# TYPEC0_Connector.net
KiCad netlist of a schematic drawn in Altium Designer
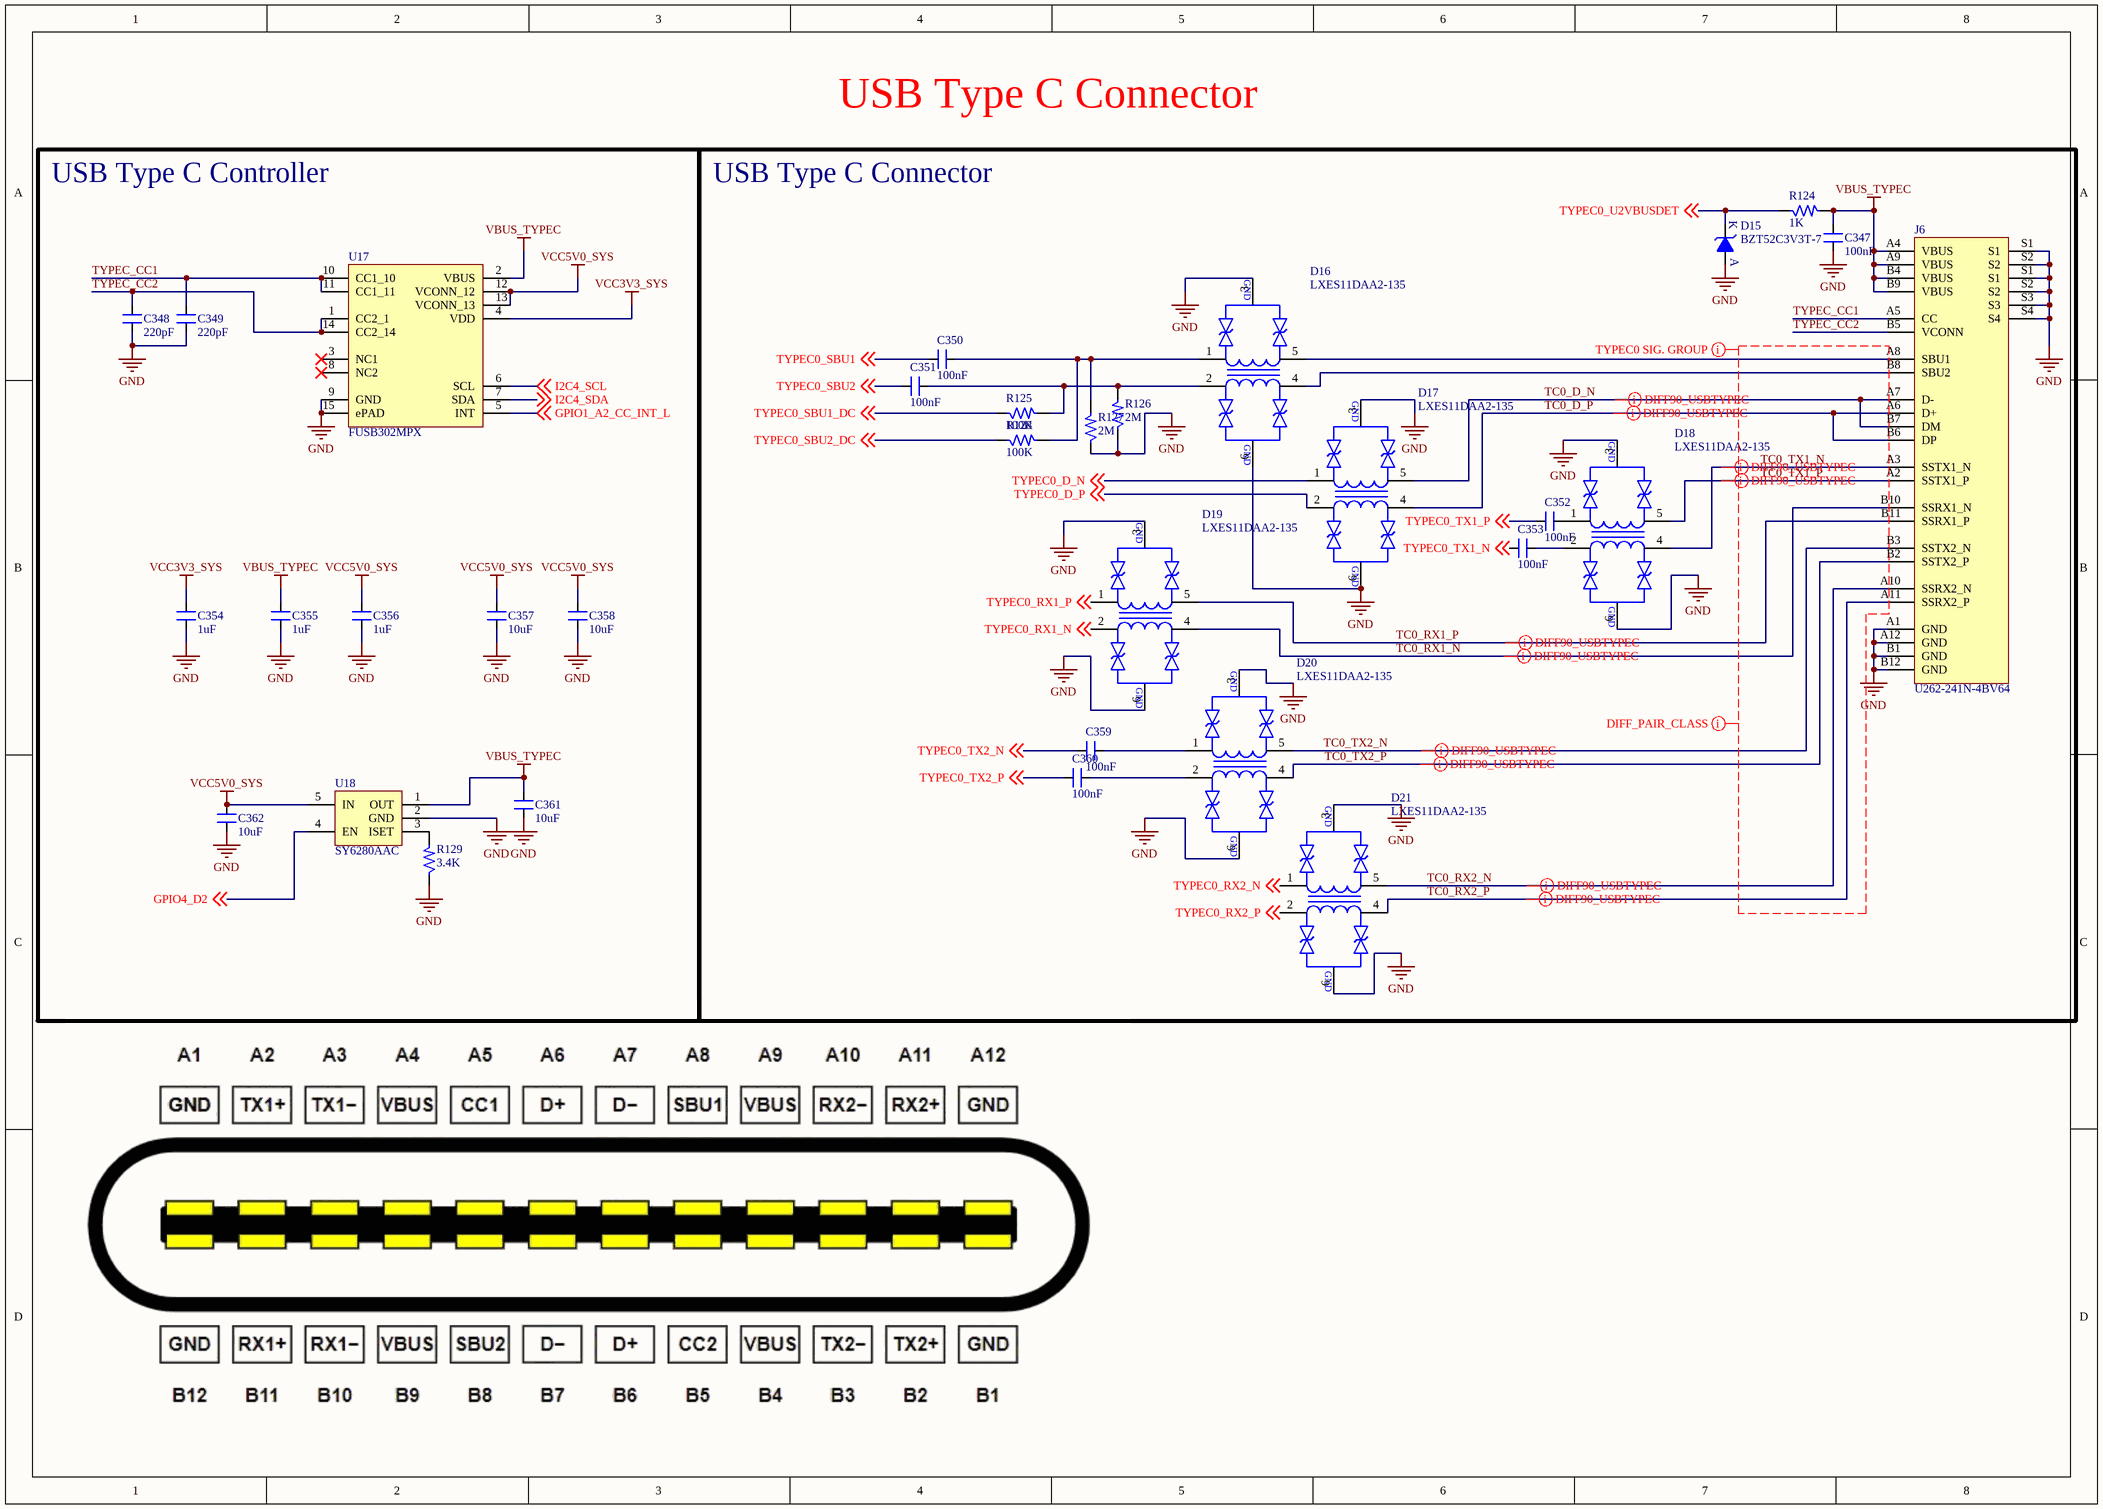
[diagram p0: TYPEC0 Connector.SchDoc]

(export (version "E")
  (design (tool "Eeschema 10.0.6"))
  (components
    (comp (ref "C347")
      (value "100nF")
      (footprint "CAP_0603")
      (description "0.1µF ±10% 10V Ceramic Capacitor X7R 0603 (1608 Metric)")
      (fields
        (field (name "MANUFACTURER") "Yageo")
        (field (name "MANUFACTURER PART NUMBER") "CC0603KRX7R6BB104")
      )
      (libsource (lib "RK3399 _Module_Schlib") (part "CAP_100nF-10V-5%-0603"))
    )
    (comp (ref "C348")
      (value "220pF")
      (footprint "CAP_0603")
      (description "220pF ±10% 10V Ceramic Capacitor X7R 0603 (1608 Metric)")
      (fields
        (field (name "MANUFACTURER") "KEMET")
        (field (name "MANUFACTURER PART NUMBER") "C0603C221K8RAC7867")
      )
      (libsource (lib "RK3399 _Module_Schlib") (part "CAP_220pF-10V-10%-0603"))
    )
    (comp (ref "C349")
      (value "220pF")
      (footprint "CAP_0603")
      (description "220pF ±10% 10V Ceramic Capacitor X7R 0603 (1608 Metric)")
      (fields
        (field (name "MANUFACTURER") "KEMET")
        (field (name "MANUFACTURER PART NUMBER") "C0603C221K8RAC7867")
      )
      (libsource (lib "RK3399 _Module_Schlib") (part "CAP_220pF-10V-10%-0603"))
    )
    (comp (ref "C350")
      (value "100nF")
      (footprint "CAP_0402")
      (description "0.1µF ±10% 10V Ceramic Capacitor X7R 0402 (1005 Metric)")
      (fields
        (field (name "MANUFACTURER") "Yageo")
        (field (name "MANUFACTURER PART NUMBER") "CC0402KRX7R6BB104")
      )
      (libsource (lib "RK3399 _Module_Schlib") (part "CAP_100nF-10V-10%-0402"))
    )
    (comp (ref "C351")
      (value "100nF")
      (footprint "CAP_0402")
      (description "0.1µF ±10% 10V Ceramic Capacitor X7R 0402 (1005 Metric)")
      (fields
        (field (name "MANUFACTURER") "Yageo")
        (field (name "MANUFACTURER PART NUMBER") "CC0402KRX7R6BB104")
      )
      (libsource (lib "RK3399 _Module_Schlib") (part "CAP_100nF-10V-10%-0402"))
    )
    (comp (ref "C352")
      (value "100nF")
      (footprint "CAP_0402")
      (description "0.1µF ±10% 10V Ceramic Capacitor X7R 0402 (1005 Metric)")
      (fields
        (field (name "MANUFACTURER") "Yageo")
        (field (name "MANUFACTURER PART NUMBER") "CC0402KRX7R6BB104")
      )
      (libsource (lib "RK3399 _Module_Schlib") (part "CAP_100nF-10V-10%-0402"))
    )
    (comp (ref "C353")
      (value "100nF")
      (footprint "CAP_0402")
      (description "0.1µF ±10% 10V Ceramic Capacitor X7R 0402 (1005 Metric)")
      (fields
        (field (name "MANUFACTURER") "Yageo")
        (field (name "MANUFACTURER PART NUMBER") "CC0402KRX7R6BB104")
      )
      (libsource (lib "RK3399 _Module_Schlib") (part "CAP_100nF-10V-10%-0402"))
    )
    (comp (ref "C354")
      (value "1uF")
      (footprint "CAP_0603")
      (description "1µF ±10% 10V Ceramic Capacitor X5R 0603 (1608 Metric)")
      (fields
        (field (name "MANUFACTURER") "Samsung Electro-Mechanics")
        (field (name "MANUFACTURER PART NUMBER") "CL10A105KP8NNNC")
      )
      (libsource (lib "RK3399 _Module_Schlib") (part "CAP_1uF-10V-5%-0603"))
    )
    (comp (ref "C355")
      (value "1uF")
      (footprint "CAP_0603")
      (description "1µF ±10% 10V Ceramic Capacitor X5R 0603 (1608 Metric)")
      (fields
        (field (name "MANUFACTURER") "Samsung Electro-Mechanics")
        (field (name "MANUFACTURER PART NUMBER") "CL10A105KP8NNNC")
      )
      (libsource (lib "RK3399 _Module_Schlib") (part "CAP_1uF-10V-5%-0603"))
    )
    (comp (ref "C356")
      (value "1uF")
      (footprint "CAP_0603")
      (description "1µF ±10% 10V Ceramic Capacitor X5R 0603 (1608 Metric)")
      (fields
        (field (name "MANUFACTURER") "Samsung Electro-Mechanics")
        (field (name "MANUFACTURER PART NUMBER") "CL10A105KP8NNNC")
      )
      (libsource (lib "RK3399 _Module_Schlib") (part "CAP_1uF-10V-5%-0603"))
    )
    (comp (ref "C357")
      (value "10uF")
      (footprint "CAP_0805")
      (description "10µF ±10% 25V Ceramic Capacitor X5R 0805 (2012 Metric)")
      (fields
        (field (name "MANUFACTURER") "Murata Electronics")
        (field (name "MANUFACTURER PART NUMBER") "GRM21BR61E106KA73K")
      )
      (libsource (lib "RK3399 _Module_Schlib") (part "CAP_10uF-25V-10%-0805"))
    )
    (comp (ref "C358")
      (value "10uF")
      (footprint "CAP_0805")
      (description "10µF ±10% 25V Ceramic Capacitor X5R 0805 (2012 Metric)")
      (fields
        (field (name "MANUFACTURER") "Murata Electronics")
        (field (name "MANUFACTURER PART NUMBER") "GRM21BR61E106KA73K")
      )
      (libsource (lib "RK3399 _Module_Schlib") (part "CAP_10uF-25V-10%-0805"))
    )
    (comp (ref "C359")
      (value "100nF")
      (footprint "CAP_0402")
      (description "0.1µF ±10% 10V Ceramic Capacitor X7R 0402 (1005 Metric)")
      (fields
        (field (name "MANUFACTURER") "Yageo")
        (field (name "MANUFACTURER PART NUMBER") "CC0402KRX7R6BB104")
      )
      (libsource (lib "RK3399 _Module_Schlib") (part "CAP_100nF-10V-10%-0402"))
    )
    (comp (ref "C360")
      (value "100nF")
      (footprint "CAP_0402")
      (description "0.1µF ±10% 10V Ceramic Capacitor X7R 0402 (1005 Metric)")
      (fields
        (field (name "MANUFACTURER") "Yageo")
        (field (name "MANUFACTURER PART NUMBER") "CC0402KRX7R6BB104")
      )
      (libsource (lib "RK3399 _Module_Schlib") (part "CAP_100nF-10V-10%-0402"))
    )
    (comp (ref "C361")
      (value "10uF")
      (footprint "CAP_0805")
      (description "10µF ±10% 25V Ceramic Capacitor X5R 0805 (2012 Metric)")
      (fields
        (field (name "MANUFACTURER") "Murata Electronics")
        (field (name "MANUFACTURER PART NUMBER") "GRM21BR61E106KA73K")
      )
      (libsource (lib "RK3399 _Module_Schlib") (part "CAP_10uF-25V-10%-0805"))
    )
    (comp (ref "C362")
      (value "10uF")
      (footprint "CAP_0805")
      (description "10µF ±10% 25V Ceramic Capacitor X5R 0805 (2012 Metric)")
      (fields
        (field (name "MANUFACTURER") "Murata Electronics")
        (field (name "MANUFACTURER PART NUMBER") "GRM21BR61E106KA73K")
      )
      (libsource (lib "RK3399 _Module_Schlib") (part "CAP_10uF-25V-10%-0805"))
    )
    (comp (ref "D15")
      (value "BZT52C3V3T-7")
      (footprint "DIO_SOD523")
      (description "Zener Diode 3.3V 300mW ±6% Surface Mount SOD-523")
      (fields (field (name "MANUFACTURER") "Diodes Incorporated"))
      (libsource (lib "RK3399 _Module_Schlib") (part "DIO-Z_3.3V-300mW-SOD-523"))
    )
    (comp (ref "D16")
      (value "LXES11DAA2-135")
      (footprint "DIO_LXES11D_SMD")
      (description "Clamp Ipp Tvs Diode Surface Mount 10-SMD")
      (fields (field (name "MANUFACTURER") "Murata Electronics"))
      (libsource (lib "RK3399 _Module_Schlib") (part "DIO-T-A_5V-6SMD"))
    )
    (comp (ref "D17")
      (value "LXES11DAA2-135")
      (footprint "DIO_LXES11D_SMD")
      (description "Clamp Ipp Tvs Diode Surface Mount 10-SMD")
      (fields (field (name "MANUFACTURER") "Murata Electronics"))
      (libsource (lib "RK3399 _Module_Schlib") (part "DIO-T-A_5V-6SMD"))
    )
    (comp (ref "D18")
      (value "LXES11DAA2-135")
      (footprint "DIO_LXES11D_SMD")
      (description "Clamp Ipp Tvs Diode Surface Mount 10-SMD")
      (fields (field (name "MANUFACTURER") "Murata Electronics"))
      (libsource (lib "RK3399 _Module_Schlib") (part "DIO-T-A_5V-6SMD"))
    )
    (comp (ref "D19")
      (value "LXES11DAA2-135")
      (footprint "DIO_LXES11D_SMD")
      (description "Clamp Ipp Tvs Diode Surface Mount 10-SMD")
      (fields (field (name "MANUFACTURER") "Murata Electronics"))
      (libsource (lib "RK3399 _Module_Schlib") (part "DIO-T-A_5V-6SMD"))
    )
    (comp (ref "D20")
      (value "LXES11DAA2-135")
      (footprint "DIO_LXES11D_SMD")
      (description "Clamp Ipp Tvs Diode Surface Mount 10-SMD")
      (fields (field (name "MANUFACTURER") "Murata Electronics"))
      (libsource (lib "RK3399 _Module_Schlib") (part "DIO-T-A_5V-6SMD"))
    )
    (comp (ref "D21")
      (value "LXES11DAA2-135")
      (footprint "DIO_LXES11D_SMD")
      (description "Clamp Ipp Tvs Diode Surface Mount 10-SMD")
      (fields (field (name "MANUFACTURER") "Murata Electronics"))
      (libsource (lib "RK3399 _Module_Schlib") (part "DIO-T-A_5V-6SMD"))
    )
    (comp (ref "J6")
      (value "U262-241N-4BV64")
      (footprint "CON24_19.64_U262-241N-4BV64_TH_RA")
      (description "USB - Type C Female 24 SMD USB Connectors RoHS")
      (fields (field (name "MANUFACTURER") "XKB Connectivity"))
      (libsource (lib "RK3399 _Module_Schlib") (part "CON-TYPEC_U262-241N-4BV64-SMD"))
    )
    (comp (ref "R124")
      (value "1K")
      (footprint "RES_0603")
      (description "1 kOhms ±1% 0.1W, 1/10W Chip Resistor 0603 (1608 Metric) Thick Film")
      (fields
        (field (name "MANUFACTURER") "Yageo")
        (field (name "MANUFACTURER PART NUMBER") "RC0603FR-071KL")
      )
      (libsource (lib "RK3399 _Module_Schlib") (part "RES_1K-0.1W-1%-0603"))
    )
    (comp (ref "R125")
      (value "100K")
      (footprint "RES_0603")
      (description "100 kOhms ±1% 0.1W, 1/10W Chip Resistor 0603 (1608 Metric) Automotive AEC-Q200 Thick Film")
      (fields
        (field (name "MANUFACTURER") "tackpole Electronics Inc")
        (field (name "MANUFACTURER PART NUMBER") "RMCF0603FT100K")
      )
      (libsource (lib "RK3399 _Module_Schlib") (part "RES_100K-0.1W-1%-0603"))
    )
    (comp (ref "R126")
      (value "2M")
      (footprint "RES_0603")
      (fields
        (field (name "MANUFACTURER") "KOA Speer Electronics, Inc.")
        (field (name "MANUFACTURER PART NUMBER") "RK73H1JTTD2004F")
      )
      (libsource (lib "RK3399 _Module_Schlib") (part "RES_2M-0.1W-1%-0603"))
    )
    (comp (ref "R127")
      (value "2M")
      (footprint "RES_0603")
      (fields
        (field (name "MANUFACTURER") "KOA Speer Electronics, Inc.")
        (field (name "MANUFACTURER PART NUMBER") "RK73H1JTTD2004F")
      )
      (libsource (lib "RK3399 _Module_Schlib") (part "RES_2M-0.1W-1%-0603"))
    )
    (comp (ref "R128")
      (value "100K")
      (footprint "RES_0603")
      (description "100 kOhms ±1% 0.1W, 1/10W Chip Resistor 0603 (1608 Metric) Automotive AEC-Q200 Thick Film")
      (fields
        (field (name "MANUFACTURER") "tackpole Electronics Inc")
        (field (name "MANUFACTURER PART NUMBER") "RMCF0603FT100K")
      )
      (libsource (lib "RK3399 _Module_Schlib") (part "RES_100K-0.1W-1%-0603"))
    )
    (comp (ref "R129")
      (value "3.4K")
      (footprint "RES_0603")
      (description "3.4 kOhms ±1% 0.1W, 1/10W Chip Resistor 0603 (1608 Metric) Automotive AEC-Q200 Thick Film")
      (fields
        (field (name "MANUFACTURER") "Stackpole Electronics Inc")
        (field (name "MANUFACTURER PART NUMBER") "RMCF0603FT3K40")
      )
      (libsource (lib "RK3399 _Module_Schlib") (part "RES_3.4K-0.1W-1%-0603"))
    )
    (comp (ref "U17")
      (value "FUSB302MPX")
      (footprint "MLP-14_98.4X98.4_SMD")
      (description "USB Controller USB 3.1 USB Interface 14-MLP (2.5x2.5)")
      (fields (field (name "MANUFACTURER") "ON Semiconductor"))
      (libsource (lib "RK3399 _Module_Schlib") (part "IC_FUSB302MPX"))
    )
    (comp (ref "U18")
      (value "SY6280AAC")
      (footprint "SOT23-5")
      (description "SOT-23-5 PMIC - Power Distribution Switches RoHS")
      (fields (field (name "MANUFACTURER") "Silergy Corp"))
      (libsource (lib "RK3399 _Module_Schlib") (part "REG-ADJ_5.5V-5.5V-1.25A-SOT-23-5"))
    )
  )
  (nets
    (net (code "1") (name "/TC0_D_N") (class "Default")
      (node (ref "D17") (pin "5") (pinfunction "5_5") (pintype "passive"))
      (node (ref "J6") (pin "A7") (pinfunction "D-_A7") (pintype "passive"))
      (node (ref "J6") (pin "B7") (pinfunction "DM_B7") (pintype "passive"))
    )
    (net (code "2") (name "/TC0_D_P") (class "Default")
      (node (ref "D17") (pin "4") (pinfunction "4_4") (pintype "passive"))
      (node (ref "J6") (pin "A6") (pinfunction "D+_A6") (pintype "passive"))
      (node (ref "J6") (pin "B6") (pinfunction "DP_B6") (pintype "passive"))
    )
    (net (code "3") (name "/TC0_RX1_N") (class "Default")
      (node (ref "D19") (pin "4") (pinfunction "4_4") (pintype "passive"))
      (node (ref "J6") (pin "B10") (pinfunction "SSRX1_N_B10") (pintype "passive"))
    )
    (net (code "4") (name "/TC0_RX1_P") (class "Default")
      (node (ref "D19") (pin "5") (pinfunction "5_5") (pintype "passive"))
      (node (ref "J6") (pin "B11") (pinfunction "SSRX1_P_B11") (pintype "passive"))
    )
    (net (code "5") (name "/TC0_RX2_N") (class "Default")
      (node (ref "D21") (pin "5") (pinfunction "5_5") (pintype "passive"))
      (node (ref "J6") (pin "A10") (pinfunction "SSRX2_N_A10") (pintype "passive"))
    )
    (net (code "6") (name "/TC0_RX2_P") (class "Default")
      (node (ref "D21") (pin "4") (pinfunction "4_4") (pintype "passive"))
      (node (ref "J6") (pin "A11") (pinfunction "SSRX2_P_A11") (pintype "passive"))
    )
    (net (code "7") (name "/TC0_TX1_N") (class "Default")
      (node (ref "D18") (pin "4") (pinfunction "4_4") (pintype "passive"))
      (node (ref "J6") (pin "A3") (pinfunction "SSTX1_N_A3") (pintype "passive"))
    )
    (net (code "8") (name "/TC0_TX1_P") (class "Default")
      (node (ref "D18") (pin "5") (pinfunction "5_5") (pintype "passive"))
      (node (ref "J6") (pin "A2") (pinfunction "SSTX1_P_A2") (pintype "passive"))
    )
    (net (code "9") (name "/TC0_TX2_N") (class "Default")
      (node (ref "D20") (pin "5") (pinfunction "5_5") (pintype "passive"))
      (node (ref "J6") (pin "B3") (pinfunction "SSTX2_N_B3") (pintype "passive"))
    )
    (net (code "10") (name "/TC0_TX2_P") (class "Default")
      (node (ref "D20") (pin "4") (pinfunction "4_4") (pintype "passive"))
      (node (ref "J6") (pin "B2") (pinfunction "SSTX2_P_B2") (pintype "passive"))
    )
    (net (code "11") (name "/TYPEC_CC1") (class "Default")
      (node (ref "C349") (pin "2") (pinfunction "2_2") (pintype "passive"))
      (node (ref "J6") (pin "A5") (pinfunction "CC_A5") (pintype "passive"))
      (node (ref "U17") (pin "10") (pinfunction "CC1_10_10") (pintype "passive"))
      (node (ref "U17") (pin "11") (pinfunction "CC1_11_11") (pintype "passive"))
    )
    (net (code "12") (name "/TYPEC_CC2") (class "Default")
      (node (ref "C348") (pin "2") (pinfunction "2_2") (pintype "passive"))
      (node (ref "J6") (pin "B5") (pinfunction "VCONN_B5") (pintype "passive"))
      (node (ref "U17") (pin "1") (pinfunction "CC2_1_1") (pintype "passive"))
      (node (ref "U17") (pin "14") (pinfunction "CC2_14_14") (pintype "passive"))
    )
    (net (code "13") (name "GND") (class "Default")
      (node (ref "C347") (pin "1") (pinfunction "1_1") (pintype "passive"))
      (node (ref "C348") (pin "1") (pinfunction "1_1") (pintype "passive"))
      (node (ref "C349") (pin "1") (pinfunction "1_1") (pintype "passive"))
      (node (ref "C354") (pin "1") (pinfunction "1_1") (pintype "passive"))
      (node (ref "C355") (pin "1") (pinfunction "1_1") (pintype "passive"))
      (node (ref "C356") (pin "1") (pinfunction "1_1") (pintype "passive"))
      (node (ref "C357") (pin "1") (pinfunction "1_1") (pintype "passive"))
      (node (ref "C358") (pin "1") (pinfunction "1_1") (pintype "passive"))
      (node (ref "C361") (pin "1") (pinfunction "1_1") (pintype "passive"))
      (node (ref "C362") (pin "1") (pinfunction "1_1") (pintype "passive"))
      (node (ref "D15") (pin "A") (pinfunction "A_A") (pintype "passive"))
      (node (ref "D16") (pin "3") (pinfunction "5_3") (pintype "passive"))
      (node (ref "D16") (pin "6") (pinfunction "6_6") (pintype "passive"))
      (node (ref "D17") (pin "3") (pinfunction "5_3") (pintype "passive"))
      (node (ref "D17") (pin "6") (pinfunction "6_6") (pintype "passive"))
      (node (ref "D18") (pin "3") (pinfunction "5_3") (pintype "passive"))
      (node (ref "D18") (pin "6") (pinfunction "6_6") (pintype "passive"))
      (node (ref "D19") (pin "3") (pinfunction "5_3") (pintype "passive"))
      (node (ref "D19") (pin "6") (pinfunction "6_6") (pintype "passive"))
      (node (ref "D20") (pin "3") (pinfunction "5_3") (pintype "passive"))
      (node (ref "D20") (pin "6") (pinfunction "6_6") (pintype "passive"))
      (node (ref "D21") (pin "3") (pinfunction "5_3") (pintype "passive"))
      (node (ref "D21") (pin "6") (pinfunction "6_6") (pintype "passive"))
      (node (ref "J6") (pin "A1") (pinfunction "GND_A1") (pintype "passive"))
      (node (ref "J6") (pin "A12") (pinfunction "GND_A12") (pintype "passive"))
      (node (ref "J6") (pin "B1") (pinfunction "GND_B1") (pintype "passive"))
      (node (ref "J6") (pin "B12") (pinfunction "GND_B12") (pintype "passive"))
      (node (ref "J6") (pin "S1") (pinfunction "S1_S1") (pintype "passive"))
      (node (ref "J6") (pin "S2") (pinfunction "S2_S2") (pintype "passive"))
      (node (ref "J6") (pin "S3") (pinfunction "S3_S3") (pintype "passive"))
      (node (ref "J6") (pin "S4") (pinfunction "S4_S4") (pintype "passive"))
      (node (ref "R126") (pin "1") (pinfunction "1_1") (pintype "passive"))
      (node (ref "R127") (pin "1") (pinfunction "1_1") (pintype "passive"))
      (node (ref "R129") (pin "1") (pinfunction "1_1") (pintype "passive"))
      (node (ref "U17") (pin "15") (pinfunction "ePAD_15") (pintype "passive"))
      (node (ref "U17") (pin "9") (pinfunction "GND_9") (pintype "passive"))
      (node (ref "U18") (pin "2") (pinfunction "GND_2") (pintype "passive"))
    )
    (net (code "14") (name "GPIO1_A2_CC_INT_L") (class "Default")
      (node (ref "U17") (pin "5") (pinfunction "INT_5") (pintype "passive"))
    )
    (net (code "15") (name "GPIO4_D2") (class "Default")
      (node (ref "U18") (pin "4") (pinfunction "EN_4") (pintype "passive"))
    )
    (net (code "16") (name "I2C4_SCL") (class "Default")
      (node (ref "U17") (pin "6") (pinfunction "SCL_6") (pintype "passive"))
    )
    (net (code "17") (name "I2C4_SDA") (class "Default")
      (node (ref "U17") (pin "7") (pinfunction "SDA_7") (pintype "passive"))
    )
    (net (code "18") (name "Net-(C350-Pad2)") (class "Default")
      (node (ref "C350") (pin "2") (pinfunction "2_2") (pintype "passive"))
      (node (ref "D16") (pin "1") (pinfunction "1_1") (pintype "passive"))
      (node (ref "R127") (pin "2") (pinfunction "2_2") (pintype "passive"))
      (node (ref "R128") (pin "2") (pinfunction "2_2") (pintype "passive"))
    )
    (net (code "19") (name "Net-(C351-Pad2)") (class "Default")
      (node (ref "C351") (pin "2") (pinfunction "2_2") (pintype "passive"))
      (node (ref "D16") (pin "2") (pinfunction "2_2") (pintype "passive"))
      (node (ref "R125") (pin "2") (pinfunction "2_2") (pintype "passive"))
      (node (ref "R126") (pin "2") (pinfunction "2_2") (pintype "passive"))
    )
    (net (code "20") (name "Net-(C352-Pad2)") (class "Default")
      (node (ref "C352") (pin "2") (pinfunction "2_2") (pintype "passive"))
      (node (ref "D18") (pin "1") (pinfunction "1_1") (pintype "passive"))
    )
    (net (code "21") (name "Net-(C353-Pad2)") (class "Default")
      (node (ref "C353") (pin "2") (pinfunction "2_2") (pintype "passive"))
      (node (ref "D18") (pin "2") (pinfunction "2_2") (pintype "passive"))
    )
    (net (code "22") (name "Net-(C359-Pad2)") (class "Default")
      (node (ref "C359") (pin "2") (pinfunction "2_2") (pintype "passive"))
      (node (ref "D20") (pin "1") (pinfunction "1_1") (pintype "passive"))
    )
    (net (code "23") (name "Net-(C360-Pad2)") (class "Default")
      (node (ref "C360") (pin "2") (pinfunction "2_2") (pintype "passive"))
      (node (ref "D20") (pin "2") (pinfunction "2_2") (pintype "passive"))
    )
    (net (code "24") (name "Net-(J6-SBU1)") (class "Default")
      (node (ref "D16") (pin "5") (pinfunction "5_5") (pintype "passive"))
      (node (ref "J6") (pin "A8") (pinfunction "SBU1_A8") (pintype "passive"))
    )
    (net (code "25") (name "Net-(J6-SBU2)") (class "Default")
      (node (ref "D16") (pin "4") (pinfunction "4_4") (pintype "passive"))
      (node (ref "J6") (pin "B8") (pinfunction "SBU2_B8") (pintype "passive"))
    )
    (net (code "26") (name "Net-(U18-ISET)") (class "Default")
      (node (ref "R129") (pin "2") (pinfunction "2_2") (pintype "passive"))
      (node (ref "U18") (pin "3") (pinfunction "ISET_3") (pintype "passive"))
    )
    (net (code "27") (name "TYPEC0_D_N") (class "Default")
      (node (ref "D17") (pin "1") (pinfunction "1_1") (pintype "passive"))
    )
    (net (code "28") (name "TYPEC0_D_P") (class "Default")
      (node (ref "D17") (pin "2") (pinfunction "2_2") (pintype "passive"))
    )
    (net (code "29") (name "TYPEC0_RX1_N") (class "Default")
      (node (ref "D19") (pin "2") (pinfunction "2_2") (pintype "passive"))
    )
    (net (code "30") (name "TYPEC0_RX1_P") (class "Default")
      (node (ref "D19") (pin "1") (pinfunction "1_1") (pintype "passive"))
    )
    (net (code "31") (name "TYPEC0_RX2_N") (class "Default")
      (node (ref "D21") (pin "1") (pinfunction "1_1") (pintype "passive"))
    )
    (net (code "32") (name "TYPEC0_RX2_P") (class "Default")
      (node (ref "D21") (pin "2") (pinfunction "2_2") (pintype "passive"))
    )
    (net (code "33") (name "TYPEC0_SBU1") (class "Default")
      (node (ref "C350") (pin "1") (pinfunction "1_1") (pintype "passive"))
    )
    (net (code "34") (name "TYPEC0_SBU1_DC") (class "Default")
      (node (ref "R125") (pin "1") (pinfunction "1_1") (pintype "passive"))
    )
    (net (code "35") (name "TYPEC0_SBU2") (class "Default")
      (node (ref "C351") (pin "1") (pinfunction "1_1") (pintype "passive"))
    )
    (net (code "36") (name "TYPEC0_SBU2_DC") (class "Default")
      (node (ref "R128") (pin "1") (pinfunction "1_1") (pintype "passive"))
    )
    (net (code "37") (name "TYPEC0_TX1_N") (class "Default")
      (node (ref "C353") (pin "1") (pinfunction "1_1") (pintype "passive"))
    )
    (net (code "38") (name "TYPEC0_TX1_P") (class "Default")
      (node (ref "C352") (pin "1") (pinfunction "1_1") (pintype "passive"))
    )
    (net (code "39") (name "TYPEC0_TX2_N") (class "Default")
      (node (ref "C359") (pin "1") (pinfunction "1_1") (pintype "passive"))
    )
    (net (code "40") (name "TYPEC0_TX2_P") (class "Default")
      (node (ref "C360") (pin "1") (pinfunction "1_1") (pintype "passive"))
    )
    (net (code "41") (name "TYPEC0_U2VBUSDET") (class "Default")
      (node (ref "D15") (pin "K") (pinfunction "K_K") (pintype "passive"))
      (node (ref "R124") (pin "1") (pinfunction "1_1") (pintype "passive"))
    )
    (net (code "42") (name "VBUS_TYPEC") (class "Default")
      (node (ref "C347") (pin "2") (pinfunction "2_2") (pintype "passive"))
      (node (ref "C355") (pin "2") (pinfunction "2_2") (pintype "passive"))
      (node (ref "C361") (pin "2") (pinfunction "2_2") (pintype "passive"))
      (node (ref "J6") (pin "A4") (pinfunction "VBUS_A4") (pintype "passive"))
      (node (ref "J6") (pin "A9") (pinfunction "VBUS_A9") (pintype "passive"))
      (node (ref "J6") (pin "B4") (pinfunction "VBUS_B4") (pintype "passive"))
      (node (ref "J6") (pin "B9") (pinfunction "VBUS_B9") (pintype "passive"))
      (node (ref "R124") (pin "2") (pinfunction "2_2") (pintype "passive"))
      (node (ref "U17") (pin "2") (pinfunction "VBUS_2") (pintype "passive"))
      (node (ref "U18") (pin "1") (pinfunction "OUT_1") (pintype "passive"))
    )
    (net (code "43") (name "VCC3V3_SYS") (class "Default")
      (node (ref "C354") (pin "2") (pinfunction "2_2") (pintype "passive"))
      (node (ref "U17") (pin "4") (pinfunction "VDD_4") (pintype "passive"))
    )
    (net (code "44") (name "VCC5V0_SYS") (class "Default")
      (node (ref "C356") (pin "2") (pinfunction "2_2") (pintype "passive"))
      (node (ref "C357") (pin "2") (pinfunction "2_2") (pintype "passive"))
      (node (ref "C358") (pin "2") (pinfunction "2_2") (pintype "passive"))
      (node (ref "C362") (pin "2") (pinfunction "2_2") (pintype "passive"))
      (node (ref "U17") (pin "12") (pinfunction "VCONN_12_12") (pintype "passive"))
      (node (ref "U17") (pin "13") (pinfunction "VCONN_13_13") (pintype "passive"))
      (node (ref "U18") (pin "5") (pinfunction "IN_5") (pintype "passive"))
    )
    (net (code "45") (name "unconnected-(U17-NC1-Pad3)") (class "Default")
      (node (ref "U17") (pin "3") (pinfunction "NC1_3") (pintype "passive+no_connect"))
    )
    (net (code "46") (name "unconnected-(U17-NC2-Pad8)") (class "Default")
      (node (ref "U17") (pin "8") (pinfunction "NC2_8") (pintype "passive+no_connect"))
    )
  )
)
